# DIOT_Template.net
KiCad netlist of a schematic drawn in Altium Designer
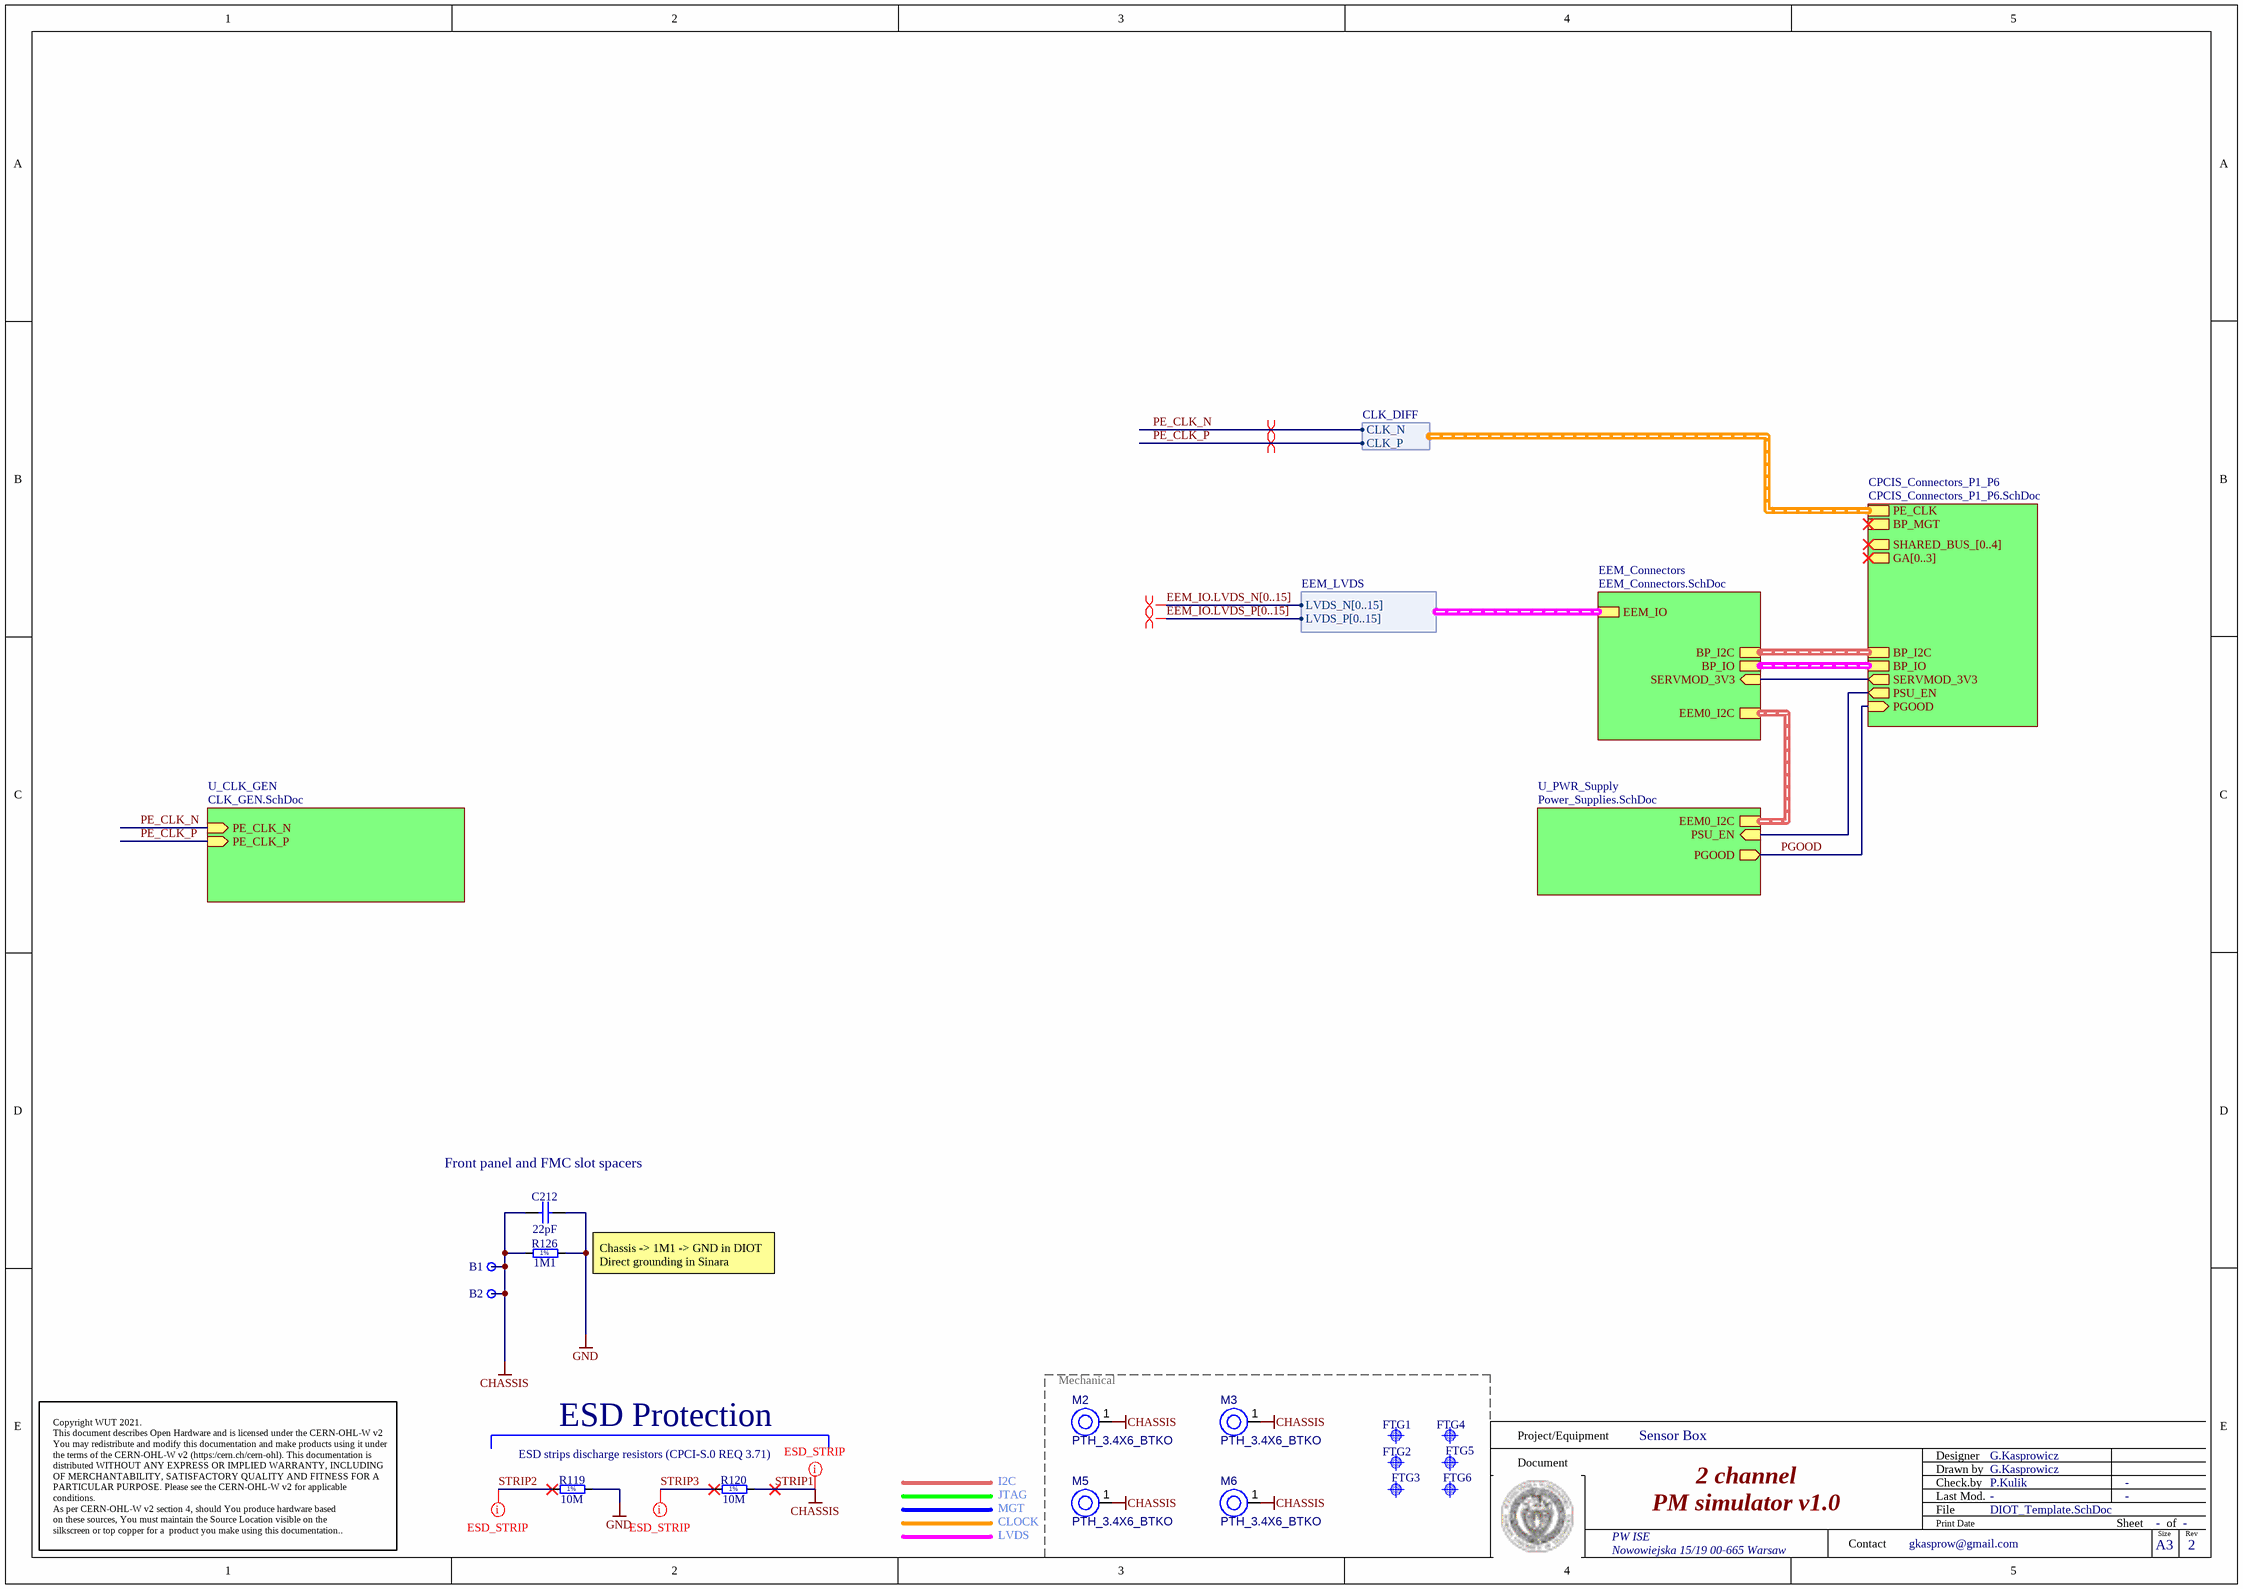
[diagram p0: DIOT_Template.SchDoc]

(export (version "E")
  (design (tool "Eeschema 10.0.6"))
  (components
    (comp (ref "B1")
      (value "Plated Hole")
      (footprint "c600h270")
      (description "Single Terminal Socket")
      (fields (field (name "PART NUMBER") "PLATED_HOLE2.7_PAD6.0") (field (name "AUTHOR") "CERN DEM HF"))
      (libsource (lib "Eletro-mechanical") (part "Single Terminal Socket"))
    )
    (comp (ref "B2")
      (value "Plated Hole")
      (footprint "c600h270")
      (description "Single Terminal Socket")
      (fields (field (name "PART NUMBER") "PLATED_HOLE2.7_PAD6.0") (field (name "AUTHOR") "CERN DEM HF"))
      (libsource (lib "Eletro-mechanical") (part "Single Terminal Socket"))
    )
    (comp (ref "C212")
      (value "22pF")
      (footprint "CAPC1005X55N")
      (description "Non-polarised capacitor")
      (fields
        (field (name "PART NUMBER") "CC0402_22PF_50V_5%_C0G")
        (field (name "VOLTAGE") "50V")
        (field (name "AUTHOR") "CERN DEM JLC")
      )
      (libsource (lib "Capacitors") (part "Capacitor - non polarized"))
    )
    (comp (ref "FTG1")
      (value "Use only in PCB")
      (footprint "FIDUCIAL_TOP_C100-200")
      (description "Fiducial Target")
      (fields (field (name "PART NUMBER") "FIDUCIAL_TARGET_C100-200") (field (name "AUTHOR") "CERN DEM JLC"))
      (libsource (lib "Eletro-mechanical") (part "Fiducial Target"))
    )
    (comp (ref "FTG2")
      (value "Use only in PCB")
      (footprint "FIDUCIAL_TOP_S100-200")
      (description "Fiducial Target")
      (fields (field (name "PART NUMBER") "FIDUCIAL_TARGET_S100-200") (field (name "AUTHOR") "CERN DEM JLC"))
      (libsource (lib "Eletro-mechanical") (part "Fiducial Target"))
    )
    (comp (ref "FTG3")
      (value "Use only in PCB")
      (footprint "FIDUCIAL_TOP_C100-200")
      (description "Fiducial Target")
      (fields (field (name "PART NUMBER") "FIDUCIAL_TARGET_C100-200") (field (name "AUTHOR") "CERN DEM JLC"))
      (libsource (lib "Eletro-mechanical") (part "Fiducial Target"))
    )
    (comp (ref "FTG4")
      (value "Use only in PCB")
      (footprint "FIDUCIAL_TOP_S100-200")
      (description "Fiducial Target")
      (fields (field (name "PART NUMBER") "FIDUCIAL_TARGET_S100-200") (field (name "AUTHOR") "CERN DEM JLC"))
      (libsource (lib "Eletro-mechanical") (part "Fiducial Target"))
    )
    (comp (ref "FTG5")
      (value "Use only in PCB")
      (footprint "FIDUCIAL_TOP_S100-200")
      (description "Fiducial Target")
      (fields (field (name "PART NUMBER") "FIDUCIAL_TARGET_S100-200") (field (name "AUTHOR") "CERN DEM JLC"))
      (libsource (lib "Eletro-mechanical") (part "Fiducial Target"))
    )
    (comp (ref "FTG6")
      (value "Use only in PCB")
      (footprint "FIDUCIAL_TOP_S100-200")
      (description "Fiducial Target")
      (fields (field (name "PART NUMBER") "FIDUCIAL_TARGET_S100-200") (field (name "AUTHOR") "CERN DEM JLC"))
      (libsource (lib "Eletro-mechanical") (part "Fiducial Target"))
    )
    (comp (ref "M2")
      (value "PTH_3.4X6_BTKO")
      (footprint "PTH-M3.4x6.0_BTKO")
      (description "PTH  Hole 3.4, 6mm pad")
      (libsource (lib "TechnoSystem Workspace") (part "PTH3.4x6.0_BTKO"))
    )
    (comp (ref "M3")
      (value "PTH_3.4X6_BTKO")
      (footprint "PTH-M3.4x6.0_BTKO")
      (description "PTH  Hole 3.4, 6mm pad")
      (libsource (lib "TechnoSystem Workspace") (part "PTH3.4x6.0_BTKO"))
    )
    (comp (ref "M5")
      (value "PTH_3.4X6_BTKO")
      (footprint "PTH-M3.4x6.0_BTKO")
      (description "PTH  Hole 3.4, 6mm pad")
      (libsource (lib "TechnoSystem Workspace") (part "PTH3.4x6.0_BTKO"))
    )
    (comp (ref "M6")
      (value "PTH_3.4X6_BTKO")
      (footprint "PTH-M3.4x6.0_BTKO")
      (description "PTH  Hole 3.4, 6mm pad")
      (libsource (lib "TechnoSystem Workspace") (part "PTH3.4x6.0_BTKO"))
    )
    (comp (ref "R119")
      (value "10M")
      (footprint "RESC2113X55N")
      (description "Resistor - 1%")
      (fields
        (field (name "PART NUMBER") "R0805_10M_1%_0.125W_100PPM_VISHAY_CRCW e3")
        (field (name "POWER") "0.125W")
        (field (name "AUTHOR") "CERN DEM BC")
      )
      (libsource (lib "Resistors") (part "Resistor - 1%"))
    )
    (comp (ref "R120")
      (value "10M")
      (footprint "RESC2113X55N")
      (description "Resistor - 1%")
      (fields
        (field (name "PART NUMBER") "R0805_10M_1%_0.125W_100PPM_VISHAY_CRCW e3")
        (field (name "POWER") "0.125W")
        (field (name "AUTHOR") "CERN DEM BC")
      )
      (libsource (lib "Resistors") (part "Resistor - 1%"))
    )
    (comp (ref "R126")
      (value "1M1")
      (footprint "RESC2012X60N")
      (description "Resistor - 1%")
      (fields
        (field (name "PART NUMBER") "R0805_1M1_1%_0.125W_100PPM")
        (field (name "MANUFACTURER") "GENERIC")
        (field (name "AUTHOR") "CERN DEM JLC")
      )
      (libsource (lib "Resistors") (part "Resistor - 1%"))
    )
  )
  (nets
    (net (code "32") (name "/STRIP2") (class "Default")
      (node (ref "R119") (pin "1") (pinfunction "1_1") (pintype "passive+no_connect"))
    )
    (net (code "33") (name "/STRIP3") (class "Default")
      (node (ref "R120") (pin "1") (pinfunction "1_1") (pintype "passive+no_connect"))
    )
    (net (code "36") (name "CHASSIS") (class "Default")
      (node (ref "B1") (pin "1") (pinfunction "1_1") (pintype "bidirectional"))
      (node (ref "B2") (pin "1") (pinfunction "1_1") (pintype "bidirectional"))
      (node (ref "C212") (pin "1") (pinfunction "1_1") (pintype "passive"))
      (node (ref "M2") (pin "1") (pinfunction "H1_1") (pintype "passive"))
      (node (ref "M3") (pin "1") (pinfunction "H1_1") (pintype "passive"))
      (node (ref "M5") (pin "1") (pinfunction "H1_1") (pintype "passive"))
      (node (ref "M6") (pin "1") (pinfunction "H1_1") (pintype "passive"))
      (node (ref "R120") (pin "2") (pinfunction "2_2") (pintype "passive"))
      (node (ref "R126") (pin "1") (pinfunction "1_1") (pintype "passive"))
    )
    (net (code "37") (name "GND") (class "Default")
      (node (ref "C212") (pin "2") (pinfunction "2_2") (pintype "passive"))
      (node (ref "R119") (pin "2") (pinfunction "2_2") (pintype "passive"))
      (node (ref "R126") (pin "2") (pinfunction "2_2") (pintype "passive"))
    )
  )
)
